# TK511_Blindkort.net
KiCad netlist of a schematic drawn in Altium Designer
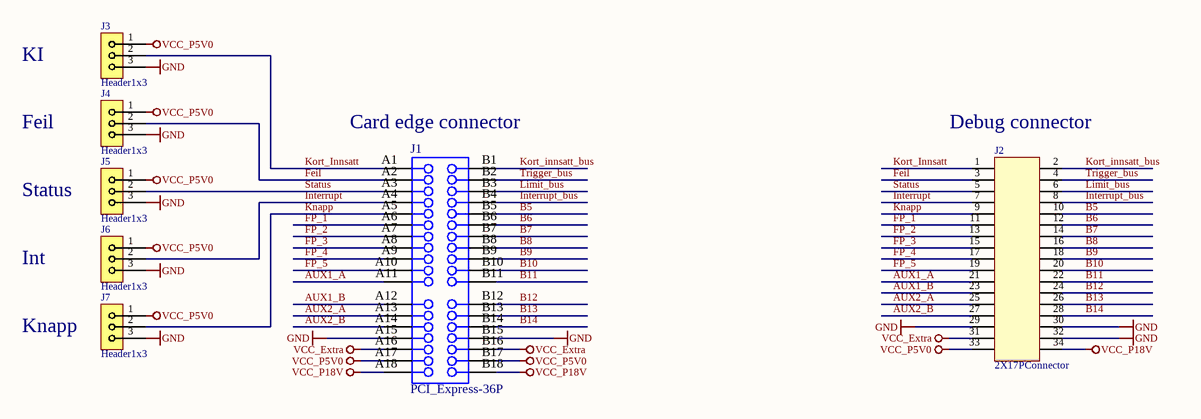
[diagram p0: TK511_Blindkort.SchDoc]

(export (version "E")
  (design (tool "Eeschema 10.0.6"))
  (components
    (comp (ref "J1")
      (value "PCI_Express-36P")
      (footprint "PCIeX1-GF-2D-1000-1K-O36")
      (description "PCI express PCB kortkankonnektor")
      (libsource (lib "OVLib_64") (part "PCI_Express-36P"))
    )
    (comp (ref "J2")
      (value "2X17PConnector")
      (footprint "HDRV34W64P254_2X17_5070X900X900B")
      (description "Header")
      (libsource (lib "OVLib_64") (part "2X17PConnector"))
    )
    (comp (ref "J3")
      (value "Header1x3")
      (footprint "HDRV3W64P254_1X3_762X254X900B")
      (description "2,54mm pitch")
      (libsource (lib "OVLib_64") (part "Header1x3"))
    )
    (comp (ref "J4")
      (value "Header1x3")
      (footprint "HDRV3W64P254_1X3_762X254X900B")
      (description "2,54mm pitch")
      (libsource (lib "OVLib_64") (part "Header1x3"))
    )
    (comp (ref "J5")
      (value "Header1x3")
      (footprint "HDRV3W64P254_1X3_762X254X900B")
      (description "2,54mm pitch")
      (libsource (lib "OVLib_64") (part "Header1x3"))
    )
    (comp (ref "J6")
      (value "Header1x3")
      (footprint "HDRV3W64P254_1X3_762X254X900B")
      (description "2,54mm pitch")
      (libsource (lib "OVLib_64") (part "Header1x3"))
    )
    (comp (ref "J7")
      (value "Header1x3")
      (footprint "HDRV3W64P254_1X3_762X254X900B")
      (description "2,54mm pitch")
      (libsource (lib "OVLib_64") (part "Header1x3"))
    )
  )
  (nets
    (net (code "1") (name "/AUX1_A") (class "Default")
      (node (ref "J1") (pin "A11") (pinfunction "A11_A11") (pintype "passive"))
      (node (ref "J2") (pin "21") (pinfunction "21_21") (pintype "passive"))
    )
    (net (code "2") (name "/AUX1_B") (class "Default")
      (node (ref "J1") (pin "A12") (pinfunction "A12_A12") (pintype "passive"))
      (node (ref "J2") (pin "23") (pinfunction "23_23") (pintype "passive"))
    )
    (net (code "3") (name "/AUX2_A") (class "Default")
      (node (ref "J1") (pin "A13") (pinfunction "A13_A13") (pintype "passive"))
      (node (ref "J2") (pin "25") (pinfunction "25_25") (pintype "passive"))
    )
    (net (code "4") (name "/AUX2_B") (class "Default")
      (node (ref "J1") (pin "A14") (pinfunction "A14_A14") (pintype "passive"))
      (node (ref "J2") (pin "27") (pinfunction "27_27") (pintype "passive"))
    )
    (net (code "5") (name "/B5") (class "Default")
      (node (ref "J1") (pin "B5") (pinfunction "B5_B5") (pintype "passive"))
      (node (ref "J2") (pin "10") (pinfunction "10_10") (pintype "passive"))
    )
    (net (code "6") (name "/B6") (class "Default")
      (node (ref "J1") (pin "B6") (pinfunction "B6_B6") (pintype "passive"))
      (node (ref "J2") (pin "12") (pinfunction "12_12") (pintype "passive"))
    )
    (net (code "7") (name "/B7") (class "Default")
      (node (ref "J1") (pin "B7") (pinfunction "B7_B7") (pintype "passive"))
      (node (ref "J2") (pin "14") (pinfunction "14_14") (pintype "passive"))
    )
    (net (code "8") (name "/B8") (class "Default")
      (node (ref "J1") (pin "B8") (pinfunction "B8_B8") (pintype "passive"))
      (node (ref "J2") (pin "16") (pinfunction "16_16") (pintype "passive"))
    )
    (net (code "9") (name "/B9") (class "Default")
      (node (ref "J1") (pin "B9") (pinfunction "B9_B9") (pintype "passive"))
      (node (ref "J2") (pin "18") (pinfunction "18_18") (pintype "passive"))
    )
    (net (code "10") (name "/B10") (class "Default")
      (node (ref "J1") (pin "B10") (pinfunction "B10_B10") (pintype "passive"))
      (node (ref "J2") (pin "20") (pinfunction "20_20") (pintype "passive"))
    )
    (net (code "11") (name "/B11") (class "Default")
      (node (ref "J1") (pin "B11") (pinfunction "B11_B11") (pintype "passive"))
      (node (ref "J2") (pin "22") (pinfunction "22_22") (pintype "passive"))
    )
    (net (code "12") (name "/B12") (class "Default")
      (node (ref "J1") (pin "B12") (pinfunction "B12_B12") (pintype "passive"))
      (node (ref "J2") (pin "24") (pinfunction "24_24") (pintype "passive"))
    )
    (net (code "13") (name "/B13") (class "Default")
      (node (ref "J1") (pin "B13") (pinfunction "B13_B13") (pintype "passive"))
      (node (ref "J2") (pin "26") (pinfunction "26_26") (pintype "passive"))
    )
    (net (code "14") (name "/B14") (class "Default")
      (node (ref "J1") (pin "B14") (pinfunction "B14_B14") (pintype "passive"))
      (node (ref "J2") (pin "28") (pinfunction "28_28") (pintype "passive"))
    )
    (net (code "15") (name "/FP_1") (class "Default")
      (node (ref "J1") (pin "A6") (pinfunction "A6_A6") (pintype "passive"))
      (node (ref "J2") (pin "11") (pinfunction "11_11") (pintype "passive"))
    )
    (net (code "16") (name "/FP_2") (class "Default")
      (node (ref "J1") (pin "A7") (pinfunction "A7_A7") (pintype "passive"))
      (node (ref "J2") (pin "13") (pinfunction "13_13") (pintype "passive"))
    )
    (net (code "17") (name "/FP_3") (class "Default")
      (node (ref "J1") (pin "A8") (pinfunction "A8_A8") (pintype "passive"))
      (node (ref "J2") (pin "15") (pinfunction "15_15") (pintype "passive"))
    )
    (net (code "18") (name "/FP_4") (class "Default")
      (node (ref "J1") (pin "A9") (pinfunction "A9_A9") (pintype "passive"))
      (node (ref "J2") (pin "17") (pinfunction "17_17") (pintype "passive"))
    )
    (net (code "19") (name "/FP_5") (class "Default")
      (node (ref "J1") (pin "A10") (pinfunction "A10_A10") (pintype "passive"))
      (node (ref "J2") (pin "19") (pinfunction "19_19") (pintype "passive"))
    )
    (net (code "20") (name "/Feil") (class "Default")
      (node (ref "J1") (pin "A2") (pinfunction "A2_A2") (pintype "passive"))
      (node (ref "J2") (pin "3") (pinfunction "3_3") (pintype "passive"))
      (node (ref "J4") (pin "2") (pinfunction "2_2") (pintype "passive"))
    )
    (net (code "21") (name "/Interrupt") (class "Default")
      (node (ref "J1") (pin "A4") (pinfunction "A4_A4") (pintype "passive"))
      (node (ref "J2") (pin "7") (pinfunction "7_7") (pintype "passive"))
      (node (ref "J6") (pin "2") (pinfunction "2_2") (pintype "passive"))
    )
    (net (code "22") (name "/Interrupt_bus") (class "Default")
      (node (ref "J1") (pin "B4") (pinfunction "B4_B4") (pintype "passive"))
      (node (ref "J2") (pin "8") (pinfunction "8_8") (pintype "passive"))
    )
    (net (code "23") (name "/Knapp") (class "Default")
      (node (ref "J1") (pin "A5") (pinfunction "A5_A5") (pintype "passive"))
      (node (ref "J2") (pin "9") (pinfunction "9_9") (pintype "passive"))
      (node (ref "J7") (pin "2") (pinfunction "2_2") (pintype "passive"))
    )
    (net (code "24") (name "/Kort_Innsatt") (class "Default")
      (node (ref "J1") (pin "A1") (pinfunction "A1_A1") (pintype "passive"))
      (node (ref "J2") (pin "1") (pinfunction "1_1") (pintype "passive"))
      (node (ref "J3") (pin "2") (pinfunction "2_2") (pintype "passive"))
    )
    (net (code "25") (name "/Kort_innsatt_bus") (class "Default")
      (node (ref "J1") (pin "B1") (pinfunction "B1_B1") (pintype "passive"))
      (node (ref "J2") (pin "2") (pinfunction "2_2") (pintype "passive"))
    )
    (net (code "26") (name "/Limit_bus") (class "Default")
      (node (ref "J1") (pin "B3") (pinfunction "B3_B3") (pintype "passive"))
      (node (ref "J2") (pin "6") (pinfunction "6_6") (pintype "passive"))
    )
    (net (code "27") (name "/Status") (class "Default")
      (node (ref "J1") (pin "A3") (pinfunction "A3_A3") (pintype "passive"))
      (node (ref "J2") (pin "5") (pinfunction "5_5") (pintype "passive"))
      (node (ref "J5") (pin "2") (pinfunction "2_2") (pintype "passive"))
    )
    (net (code "28") (name "/Trigger_bus") (class "Default")
      (node (ref "J1") (pin "B2") (pinfunction "B2_B2") (pintype "passive"))
      (node (ref "J2") (pin "4") (pinfunction "4_4") (pintype "passive"))
    )
    (net (code "29") (name "GND") (class "Default")
      (node (ref "J1") (pin "A15") (pinfunction "A15_A15") (pintype "passive"))
      (node (ref "J1") (pin "B15") (pinfunction "B15_B15") (pintype "passive"))
      (node (ref "J2") (pin "29") (pinfunction "29_29") (pintype "passive"))
      (node (ref "J2") (pin "30") (pinfunction "30_30") (pintype "passive"))
      (node (ref "J2") (pin "32") (pinfunction "32_32") (pintype "passive"))
      (node (ref "J3") (pin "3") (pinfunction "3_3") (pintype "passive"))
      (node (ref "J4") (pin "3") (pinfunction "3_3") (pintype "passive"))
      (node (ref "J5") (pin "3") (pinfunction "3_3") (pintype "passive"))
      (node (ref "J6") (pin "3") (pinfunction "3_3") (pintype "passive"))
      (node (ref "J7") (pin "3") (pinfunction "3_3") (pintype "passive"))
    )
    (net (code "30") (name "VCC_Extra") (class "Default")
      (node (ref "J1") (pin "A16") (pinfunction "A16_A16") (pintype "passive"))
      (node (ref "J1") (pin "B16") (pinfunction "B16_B16") (pintype "passive"))
      (node (ref "J2") (pin "31") (pinfunction "31_31") (pintype "passive"))
    )
    (net (code "31") (name "VCC_P5V0") (class "Default")
      (node (ref "J1") (pin "A17") (pinfunction "A17_A17") (pintype "passive"))
      (node (ref "J1") (pin "B17") (pinfunction "B17_B17") (pintype "passive"))
      (node (ref "J2") (pin "33") (pinfunction "33_33") (pintype "passive"))
      (node (ref "J3") (pin "1") (pinfunction "1_1") (pintype "passive"))
      (node (ref "J4") (pin "1") (pinfunction "1_1") (pintype "passive"))
      (node (ref "J5") (pin "1") (pinfunction "1_1") (pintype "passive"))
      (node (ref "J6") (pin "1") (pinfunction "1_1") (pintype "passive"))
      (node (ref "J7") (pin "1") (pinfunction "1_1") (pintype "passive"))
    )
    (net (code "32") (name "VCC_P18V") (class "Default")
      (node (ref "J1") (pin "A18") (pinfunction "A18_A18") (pintype "passive"))
      (node (ref "J1") (pin "B18") (pinfunction "B18_B18") (pintype "passive"))
      (node (ref "J2") (pin "34") (pinfunction "34_34") (pintype "passive"))
    )
  )
)
